# KeyboardMoudle1.net
KiCad netlist of a schematic drawn in Altium Designer
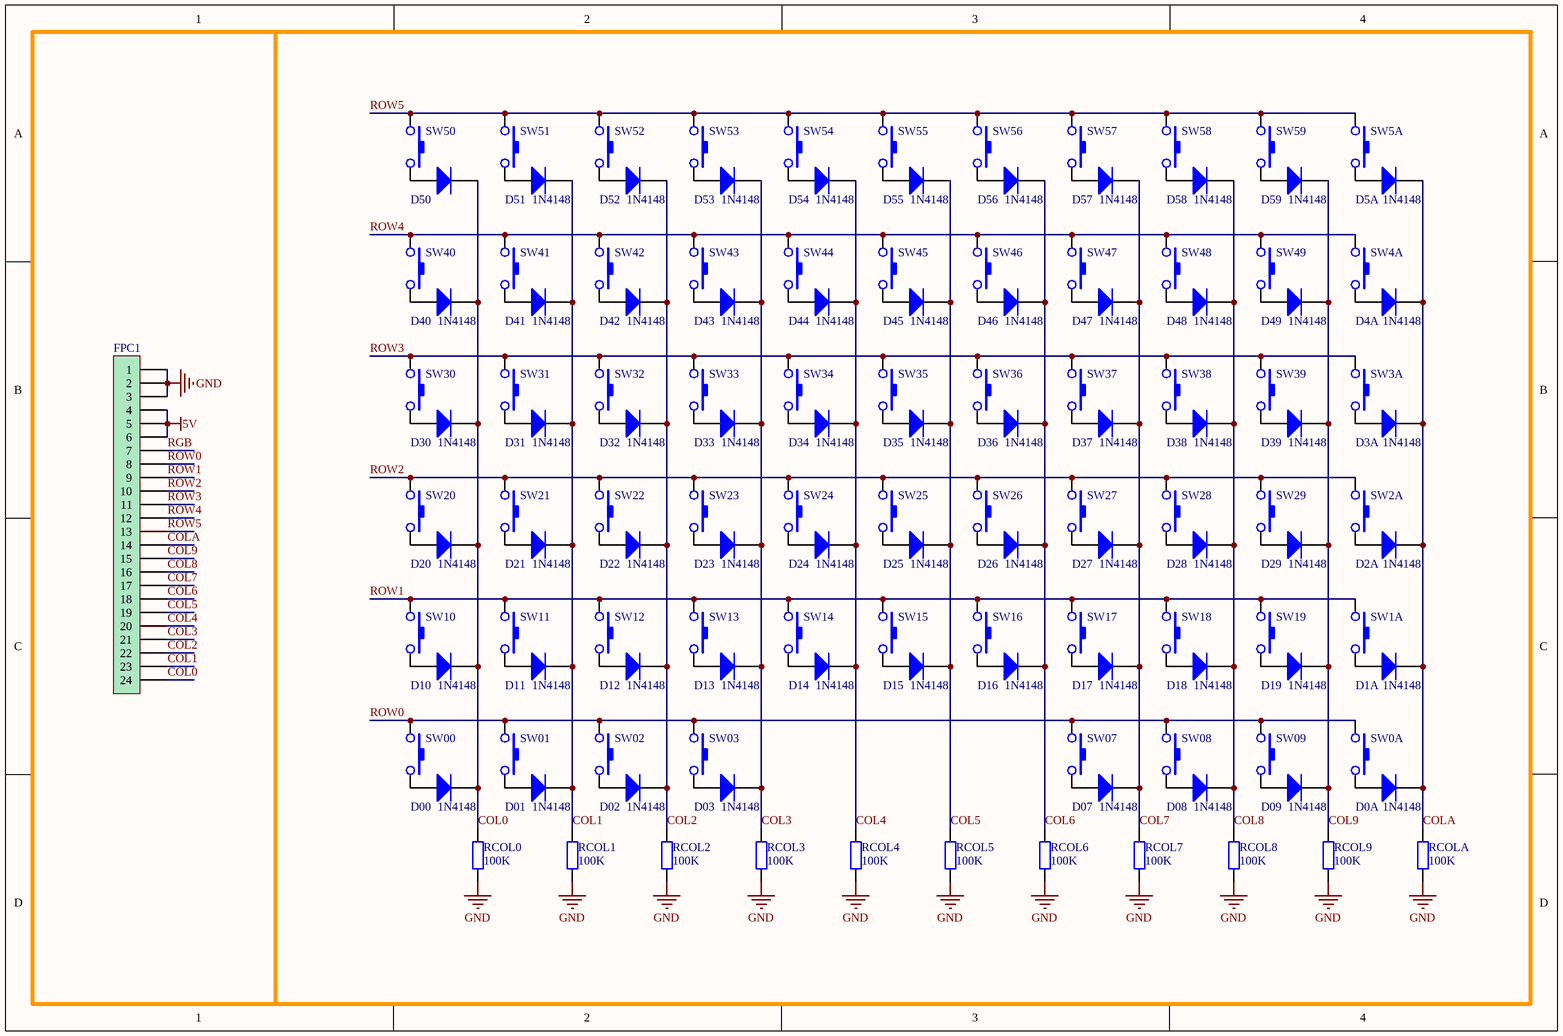
[diagram p0: KeyboardMoudle1.SchDoc]

(export (version "E")
  (design (tool "Eeschema 10.0.6"))
  (components
    (comp (ref "D00")
      (value "1N4148")
      (footprint "SOD523")
      (description "开关二极管")
      (libsource (lib "MT_Device") (part "DIO_1N4148_SOD523"))
    )
    (comp (ref "D0A")
      (value "1N4148")
      (footprint "SOD523")
      (description "开关二极管")
      (libsource (lib "MT_Device") (part "DIO_1N4148_SOD523"))
    )
    (comp (ref "D01")
      (value "1N4148")
      (footprint "SOD523")
      (description "开关二极管")
      (libsource (lib "MT_Device") (part "DIO_1N4148_SOD523"))
    )
    (comp (ref "D1A")
      (value "1N4148")
      (footprint "SOD523")
      (description "开关二极管")
      (libsource (lib "MT_Device") (part "DIO_1N4148_SOD523"))
    )
    (comp (ref "D02")
      (value "1N4148")
      (footprint "SOD523")
      (description "开关二极管")
      (libsource (lib "MT_Device") (part "DIO_1N4148_SOD523"))
    )
    (comp (ref "D2A")
      (value "1N4148")
      (footprint "SOD523")
      (description "开关二极管")
      (libsource (lib "MT_Device") (part "DIO_1N4148_SOD523"))
    )
    (comp (ref "D03")
      (value "1N4148")
      (footprint "SOD523")
      (description "开关二极管")
      (libsource (lib "MT_Device") (part "DIO_1N4148_SOD523"))
    )
    (comp (ref "D3A")
      (value "1N4148")
      (footprint "SOD523")
      (description "开关二极管")
      (libsource (lib "MT_Device") (part "DIO_1N4148_SOD523"))
    )
    (comp (ref "D4A")
      (value "1N4148")
      (footprint "SOD523")
      (description "开关二极管")
      (libsource (lib "MT_Device") (part "DIO_1N4148_SOD523"))
    )
    (comp (ref "D5A")
      (value "1N4148")
      (footprint "SOD523")
      (description "开关二极管")
      (libsource (lib "MT_Device") (part "DIO_1N4148_SOD523"))
    )
    (comp (ref "D07")
      (value "1N4148")
      (footprint "SOD523")
      (description "开关二极管")
      (libsource (lib "MT_Device") (part "DIO_1N4148_SOD523"))
    )
    (comp (ref "D08")
      (value "1N4148")
      (footprint "SOD523")
      (description "开关二极管")
      (libsource (lib "MT_Device") (part "DIO_1N4148_SOD523"))
    )
    (comp (ref "D09")
      (value "1N4148")
      (footprint "SOD523")
      (description "开关二极管")
      (libsource (lib "MT_Device") (part "DIO_1N4148_SOD523"))
    )
    (comp (ref "D10")
      (value "1N4148")
      (footprint "SOD523")
      (description "开关二极管")
      (libsource (lib "MT_Device") (part "DIO_1N4148_SOD523"))
    )
    (comp (ref "D11")
      (value "1N4148")
      (footprint "SOD523")
      (description "开关二极管")
      (libsource (lib "MT_Device") (part "DIO_1N4148_SOD523"))
    )
    (comp (ref "D12")
      (value "1N4148")
      (footprint "SOD523")
      (description "开关二极管")
      (libsource (lib "MT_Device") (part "DIO_1N4148_SOD523"))
    )
    (comp (ref "D13")
      (value "1N4148")
      (footprint "SOD523")
      (description "开关二极管")
      (libsource (lib "MT_Device") (part "DIO_1N4148_SOD523"))
    )
    (comp (ref "D14")
      (value "1N4148")
      (footprint "SOD523")
      (description "开关二极管")
      (libsource (lib "MT_Device") (part "DIO_1N4148_SOD523"))
    )
    (comp (ref "D15")
      (value "1N4148")
      (footprint "SOD523")
      (description "开关二极管")
      (libsource (lib "MT_Device") (part "DIO_1N4148_SOD523"))
    )
    (comp (ref "D16")
      (value "1N4148")
      (footprint "SOD523")
      (description "开关二极管")
      (libsource (lib "MT_Device") (part "DIO_1N4148_SOD523"))
    )
    (comp (ref "D17")
      (value "1N4148")
      (footprint "SOD523")
      (description "开关二极管")
      (libsource (lib "MT_Device") (part "DIO_1N4148_SOD523"))
    )
    (comp (ref "D18")
      (value "1N4148")
      (footprint "SOD523")
      (description "开关二极管")
      (libsource (lib "MT_Device") (part "DIO_1N4148_SOD523"))
    )
    (comp (ref "D19")
      (value "1N4148")
      (footprint "SOD523")
      (description "开关二极管")
      (libsource (lib "MT_Device") (part "DIO_1N4148_SOD523"))
    )
    (comp (ref "D20")
      (value "1N4148")
      (footprint "SOD523")
      (description "开关二极管")
      (libsource (lib "MT_Device") (part "DIO_1N4148_SOD523"))
    )
    (comp (ref "D21")
      (value "1N4148")
      (footprint "SOD523")
      (description "开关二极管")
      (libsource (lib "MT_Device") (part "DIO_1N4148_SOD523"))
    )
    (comp (ref "D22")
      (value "1N4148")
      (footprint "SOD523")
      (description "开关二极管")
      (libsource (lib "MT_Device") (part "DIO_1N4148_SOD523"))
    )
    (comp (ref "D23")
      (value "1N4148")
      (footprint "SOD523")
      (description "开关二极管")
      (libsource (lib "MT_Device") (part "DIO_1N4148_SOD523"))
    )
    (comp (ref "D24")
      (value "1N4148")
      (footprint "SOD523")
      (description "开关二极管")
      (libsource (lib "MT_Device") (part "DIO_1N4148_SOD523"))
    )
    (comp (ref "D25")
      (value "1N4148")
      (footprint "SOD523")
      (description "开关二极管")
      (libsource (lib "MT_Device") (part "DIO_1N4148_SOD523"))
    )
    (comp (ref "D26")
      (value "1N4148")
      (footprint "SOD523")
      (description "开关二极管")
      (libsource (lib "MT_Device") (part "DIO_1N4148_SOD523"))
    )
    (comp (ref "D27")
      (value "1N4148")
      (footprint "SOD523")
      (description "开关二极管")
      (libsource (lib "MT_Device") (part "DIO_1N4148_SOD523"))
    )
    (comp (ref "D28")
      (value "1N4148")
      (footprint "SOD523")
      (description "开关二极管")
      (libsource (lib "MT_Device") (part "DIO_1N4148_SOD523"))
    )
    (comp (ref "D29")
      (value "1N4148")
      (footprint "SOD523")
      (description "开关二极管")
      (libsource (lib "MT_Device") (part "DIO_1N4148_SOD523"))
    )
    (comp (ref "D30")
      (value "1N4148")
      (footprint "SOD523")
      (description "开关二极管")
      (libsource (lib "MT_Device") (part "DIO_1N4148_SOD523"))
    )
    (comp (ref "D31")
      (value "1N4148")
      (footprint "SOD523")
      (description "开关二极管")
      (libsource (lib "MT_Device") (part "DIO_1N4148_SOD523"))
    )
    (comp (ref "D32")
      (value "1N4148")
      (footprint "SOD523")
      (description "开关二极管")
      (libsource (lib "MT_Device") (part "DIO_1N4148_SOD523"))
    )
    (comp (ref "D33")
      (value "1N4148")
      (footprint "SOD523")
      (description "开关二极管")
      (libsource (lib "MT_Device") (part "DIO_1N4148_SOD523"))
    )
    (comp (ref "D34")
      (value "1N4148")
      (footprint "SOD523")
      (description "开关二极管")
      (libsource (lib "MT_Device") (part "DIO_1N4148_SOD523"))
    )
    (comp (ref "D35")
      (value "1N4148")
      (footprint "SOD523")
      (description "开关二极管")
      (libsource (lib "MT_Device") (part "DIO_1N4148_SOD523"))
    )
    (comp (ref "D36")
      (value "1N4148")
      (footprint "SOD523")
      (description "开关二极管")
      (libsource (lib "MT_Device") (part "DIO_1N4148_SOD523"))
    )
    (comp (ref "D37")
      (value "1N4148")
      (footprint "SOD523")
      (description "开关二极管")
      (libsource (lib "MT_Device") (part "DIO_1N4148_SOD523"))
    )
    (comp (ref "D38")
      (value "1N4148")
      (footprint "SOD523")
      (description "开关二极管")
      (libsource (lib "MT_Device") (part "DIO_1N4148_SOD523"))
    )
    (comp (ref "D39")
      (value "1N4148")
      (footprint "SOD523")
      (description "开关二极管")
      (libsource (lib "MT_Device") (part "DIO_1N4148_SOD523"))
    )
    (comp (ref "D40")
      (value "1N4148")
      (footprint "SOD523")
      (description "开关二极管")
      (libsource (lib "MT_Device") (part "DIO_1N4148_SOD523"))
    )
    (comp (ref "D41")
      (value "1N4148")
      (footprint "SOD523")
      (description "开关二极管")
      (libsource (lib "MT_Device") (part "DIO_1N4148_SOD523"))
    )
    (comp (ref "D42")
      (value "1N4148")
      (footprint "SOD523")
      (description "开关二极管")
      (libsource (lib "MT_Device") (part "DIO_1N4148_SOD523"))
    )
    (comp (ref "D43")
      (value "1N4148")
      (footprint "SOD523")
      (description "开关二极管")
      (libsource (lib "MT_Device") (part "DIO_1N4148_SOD523"))
    )
    (comp (ref "D44")
      (value "1N4148")
      (footprint "SOD523")
      (description "开关二极管")
      (libsource (lib "MT_Device") (part "DIO_1N4148_SOD523"))
    )
    (comp (ref "D45")
      (value "1N4148")
      (footprint "SOD523")
      (description "开关二极管")
      (libsource (lib "MT_Device") (part "DIO_1N4148_SOD523"))
    )
    (comp (ref "D46")
      (value "1N4148")
      (footprint "SOD523")
      (description "开关二极管")
      (libsource (lib "MT_Device") (part "DIO_1N4148_SOD523"))
    )
    (comp (ref "D47")
      (value "1N4148")
      (footprint "SOD523")
      (description "开关二极管")
      (libsource (lib "MT_Device") (part "DIO_1N4148_SOD523"))
    )
    (comp (ref "D48")
      (value "1N4148")
      (footprint "SOD523")
      (description "开关二极管")
      (libsource (lib "MT_Device") (part "DIO_1N4148_SOD523"))
    )
    (comp (ref "D49")
      (value "1N4148")
      (footprint "SOD523")
      (description "开关二极管")
      (libsource (lib "MT_Device") (part "DIO_1N4148_SOD523"))
    )
    (comp (ref "D50")
      (value "~")
      (footprint "SOD523")
      (description "开关二极管")
      (libsource (lib "MT_Device") (part "DIO_1N4148_SOD523"))
    )
    (comp (ref "D51")
      (value "1N4148")
      (footprint "SOD523")
      (description "开关二极管")
      (libsource (lib "MT_Device") (part "DIO_1N4148_SOD523"))
    )
    (comp (ref "D52")
      (value "1N4148")
      (footprint "SOD523")
      (description "开关二极管")
      (libsource (lib "MT_Device") (part "DIO_1N4148_SOD523"))
    )
    (comp (ref "D53")
      (value "1N4148")
      (footprint "SOD523")
      (description "开关二极管")
      (libsource (lib "MT_Device") (part "DIO_1N4148_SOD523"))
    )
    (comp (ref "D54")
      (value "1N4148")
      (footprint "SOD523")
      (description "开关二极管")
      (libsource (lib "MT_Device") (part "DIO_1N4148_SOD523"))
    )
    (comp (ref "D55")
      (value "1N4148")
      (footprint "SOD523")
      (description "开关二极管")
      (libsource (lib "MT_Device") (part "DIO_1N4148_SOD523"))
    )
    (comp (ref "D56")
      (value "1N4148")
      (footprint "SOD523")
      (description "开关二极管")
      (libsource (lib "MT_Device") (part "DIO_1N4148_SOD523"))
    )
    (comp (ref "D57")
      (value "1N4148")
      (footprint "SOD523")
      (description "开关二极管")
      (libsource (lib "MT_Device") (part "DIO_1N4148_SOD523"))
    )
    (comp (ref "D58")
      (value "1N4148")
      (footprint "SOD523")
      (description "开关二极管")
      (libsource (lib "MT_Device") (part "DIO_1N4148_SOD523"))
    )
    (comp (ref "D59")
      (value "1N4148")
      (footprint "SOD523")
      (description "开关二极管")
      (libsource (lib "MT_Device") (part "DIO_1N4148_SOD523"))
    )
    (comp (ref "FPC1")
      (value "FPC_0.5_24P")
      (footprint "FPC_0.5_24PIN")
      (description "FPC 0.5 24Pin")
      (libsource (lib "MT_Connector") (part "FPC_0.5_24P"))
    )
    (comp (ref "RCOL0")
      (value "100K")
      (footprint "R_0603")
      (description "电阻 0603")
      (libsource (lib "MT_Device") (part "RES_0603"))
    )
    (comp (ref "RCOL1")
      (value "100K")
      (footprint "R_0603")
      (description "电阻 0603")
      (libsource (lib "MT_Device") (part "RES_0603"))
    )
    (comp (ref "RCOL2")
      (value "100K")
      (footprint "R_0603")
      (description "电阻 0603")
      (libsource (lib "MT_Device") (part "RES_0603"))
    )
    (comp (ref "RCOL3")
      (value "100K")
      (footprint "R_0603")
      (description "电阻 0603")
      (libsource (lib "MT_Device") (part "RES_0603"))
    )
    (comp (ref "RCOL4")
      (value "100K")
      (footprint "R_0603")
      (description "电阻 0603")
      (libsource (lib "MT_Device") (part "RES_0603"))
    )
    (comp (ref "RCOL5")
      (value "100K")
      (footprint "R_0603")
      (description "电阻 0603")
      (libsource (lib "MT_Device") (part "RES_0603"))
    )
    (comp (ref "RCOL6")
      (value "100K")
      (footprint "R_0603")
      (description "电阻 0603")
      (libsource (lib "MT_Device") (part "RES_0603"))
    )
    (comp (ref "RCOL7")
      (value "100K")
      (footprint "R_0603")
      (description "电阻 0603")
      (libsource (lib "MT_Device") (part "RES_0603"))
    )
    (comp (ref "RCOL8")
      (value "100K")
      (footprint "R_0603")
      (description "电阻 0603")
      (libsource (lib "MT_Device") (part "RES_0603"))
    )
    (comp (ref "RCOL9")
      (value "100K")
      (footprint "R_0603")
      (description "电阻 0603")
      (libsource (lib "MT_Device") (part "RES_0603"))
    )
    (comp (ref "RCOLA")
      (value "100K")
      (footprint "R_0603")
      (description "电阻 0603")
      (libsource (lib "MT_Device") (part "RES_0603"))
    )
    (comp (ref "SW00")
      (value "KAILH")
      (footprint "KAILH_1350_HOTSWAP")
      (description "凯华机械矮轴1350用热插拔轴座")
      (libsource (lib "MT_Device") (part "SWITCH_KAILH_1350"))
    )
    (comp (ref "SW0A")
      (value "KAILH")
      (footprint "KAILH_1350_HOTSWAP")
      (description "凯华机械矮轴1350用热插拔轴座")
      (libsource (lib "MT_Device") (part "SWITCH_KAILH_1350"))
    )
    (comp (ref "SW01")
      (value "KAILH")
      (footprint "KAILH_1350_HOTSWAP")
      (description "凯华机械矮轴1350用热插拔轴座")
      (libsource (lib "MT_Device") (part "SWITCH_KAILH_1350"))
    )
    (comp (ref "SW1A")
      (value "KAILH")
      (footprint "KAILH_1350_HOTSWAP")
      (description "凯华机械矮轴1350用热插拔轴座")
      (libsource (lib "MT_Device") (part "SWITCH_KAILH_1350"))
    )
    (comp (ref "SW02")
      (value "KAILH")
      (footprint "KAILH_1350_HOTSWAP")
      (description "凯华机械矮轴1350用热插拔轴座")
      (libsource (lib "MT_Device") (part "SWITCH_KAILH_1350"))
    )
    (comp (ref "SW2A")
      (value "KAILH")
      (footprint "KAILH_1350_HOTSWAP")
      (description "凯华机械矮轴1350用热插拔轴座")
      (libsource (lib "MT_Device") (part "SWITCH_KAILH_1350"))
    )
    (comp (ref "SW03")
      (value "KAILH")
      (footprint "KAILH_1350_HOTSWAP")
      (description "凯华机械矮轴1350用热插拔轴座")
      (libsource (lib "MT_Device") (part "SWITCH_KAILH_1350"))
    )
    (comp (ref "SW3A")
      (value "KAILH")
      (footprint "KAILH_1350_HOTSWAP")
      (description "凯华机械矮轴1350用热插拔轴座")
      (libsource (lib "MT_Device") (part "SWITCH_KAILH_1350"))
    )
    (comp (ref "SW4A")
      (value "KAILH")
      (footprint "KAILH_1350_HOTSWAP")
      (description "凯华机械矮轴1350用热插拔轴座")
      (libsource (lib "MT_Device") (part "SWITCH_KAILH_1350"))
    )
    (comp (ref "SW5A")
      (value "KAILH")
      (footprint "KAILH_1350_HOTSWAP")
      (description "凯华机械矮轴1350用热插拔轴座")
      (libsource (lib "MT_Device") (part "SWITCH_KAILH_1350"))
    )
    (comp (ref "SW07")
      (value "KAILH")
      (footprint "KAILH_1350_HOTSWAP")
      (description "凯华机械矮轴1350用热插拔轴座")
      (libsource (lib "MT_Device") (part "SWITCH_KAILH_1350"))
    )
    (comp (ref "SW08")
      (value "KAILH")
      (footprint "KAILH_1350_HOTSWAP")
      (description "凯华机械矮轴1350用热插拔轴座")
      (libsource (lib "MT_Device") (part "SWITCH_KAILH_1350"))
    )
    (comp (ref "SW09")
      (value "KAILH")
      (footprint "KAILH_1350_HOTSWAP")
      (description "凯华机械矮轴1350用热插拔轴座")
      (libsource (lib "MT_Device") (part "SWITCH_KAILH_1350"))
    )
    (comp (ref "SW10")
      (value "KAILH")
      (footprint "KAILH_1350_HOTSWAP")
      (description "凯华机械矮轴1350用热插拔轴座")
      (libsource (lib "MT_Device") (part "SWITCH_KAILH_1350"))
    )
    (comp (ref "SW11")
      (value "KAILH")
      (footprint "KAILH_1350_HOTSWAP")
      (description "凯华机械矮轴1350用热插拔轴座")
      (libsource (lib "MT_Device") (part "SWITCH_KAILH_1350"))
    )
    (comp (ref "SW12")
      (value "KAILH")
      (footprint "KAILH_1350_HOTSWAP")
      (description "凯华机械矮轴1350用热插拔轴座")
      (libsource (lib "MT_Device") (part "SWITCH_KAILH_1350"))
    )
    (comp (ref "SW13")
      (value "KAILH")
      (footprint "KAILH_1350_HOTSWAP")
      (description "凯华机械矮轴1350用热插拔轴座")
      (libsource (lib "MT_Device") (part "SWITCH_KAILH_1350"))
    )
    (comp (ref "SW14")
      (value "KAILH")
      (footprint "KAILH_1350_HOTSWAP")
      (description "凯华机械矮轴1350用热插拔轴座")
      (libsource (lib "MT_Device") (part "SWITCH_KAILH_1350"))
    )
    (comp (ref "SW15")
      (value "KAILH")
      (footprint "KAILH_1350_HOTSWAP")
      (description "凯华机械矮轴1350用热插拔轴座")
      (libsource (lib "MT_Device") (part "SWITCH_KAILH_1350"))
    )
    (comp (ref "SW16")
      (value "KAILH")
      (footprint "KAILH_1350_HOTSWAP")
      (description "凯华机械矮轴1350用热插拔轴座")
      (libsource (lib "MT_Device") (part "SWITCH_KAILH_1350"))
    )
    (comp (ref "SW17")
      (value "KAILH")
      (footprint "KAILH_1350_HOTSWAP")
      (description "凯华机械矮轴1350用热插拔轴座")
      (libsource (lib "MT_Device") (part "SWITCH_KAILH_1350"))
    )
    (comp (ref "SW18")
      (value "KAILH")
      (footprint "KAILH_1350_HOTSWAP")
      (description "凯华机械矮轴1350用热插拔轴座")
      (libsource (lib "MT_Device") (part "SWITCH_KAILH_1350"))
    )
    (comp (ref "SW19")
      (value "KAILH")
      (footprint "KAILH_1350_HOTSWAP")
      (description "凯华机械矮轴1350用热插拔轴座")
      (libsource (lib "MT_Device") (part "SWITCH_KAILH_1350"))
    )
    (comp (ref "SW20")
      (value "KAILH")
      (footprint "KAILH_1350_HOTSWAP")
      (description "凯华机械矮轴1350用热插拔轴座")
      (libsource (lib "MT_Device") (part "SWITCH_KAILH_1350"))
    )
    (comp (ref "SW21")
      (value "KAILH")
      (footprint "KAILH_1350_HOTSWAP")
      (description "凯华机械矮轴1350用热插拔轴座")
      (libsource (lib "MT_Device") (part "SWITCH_KAILH_1350"))
    )
    (comp (ref "SW22")
      (value "KAILH")
      (footprint "KAILH_1350_HOTSWAP")
      (description "凯华机械矮轴1350用热插拔轴座")
      (libsource (lib "MT_Device") (part "SWITCH_KAILH_1350"))
    )
    (comp (ref "SW23")
      (value "KAILH")
      (footprint "KAILH_1350_HOTSWAP")
      (description "凯华机械矮轴1350用热插拔轴座")
      (libsource (lib "MT_Device") (part "SWITCH_KAILH_1350"))
    )
    (comp (ref "SW24")
      (value "KAILH")
      (footprint "KAILH_1350_HOTSWAP")
      (description "凯华机械矮轴1350用热插拔轴座")
      (libsource (lib "MT_Device") (part "SWITCH_KAILH_1350"))
    )
    (comp (ref "SW25")
      (value "KAILH")
      (footprint "KAILH_1350_HOTSWAP")
      (description "凯华机械矮轴1350用热插拔轴座")
      (libsource (lib "MT_Device") (part "SWITCH_KAILH_1350"))
    )
    (comp (ref "SW26")
      (value "KAILH")
      (footprint "KAILH_1350_HOTSWAP")
      (description "凯华机械矮轴1350用热插拔轴座")
      (libsource (lib "MT_Device") (part "SWITCH_KAILH_1350"))
    )
    (comp (ref "SW27")
      (value "KAILH")
      (footprint "KAILH_1350_HOTSWAP")
      (description "凯华机械矮轴1350用热插拔轴座")
      (libsource (lib "MT_Device") (part "SWITCH_KAILH_1350"))
    )
    (comp (ref "SW28")
      (value "KAILH")
      (footprint "KAILH_1350_HOTSWAP")
      (description "凯华机械矮轴1350用热插拔轴座")
      (libsource (lib "MT_Device") (part "SWITCH_KAILH_1350"))
    )
    (comp (ref "SW29")
      (value "KAILH")
      (footprint "KAILH_1350_HOTSWAP")
      (description "凯华机械矮轴1350用热插拔轴座")
      (libsource (lib "MT_Device") (part "SWITCH_KAILH_1350"))
    )
    (comp (ref "SW30")
      (value "KAILH")
      (footprint "KAILH_1350_HOTSWAP")
      (description "凯华机械矮轴1350用热插拔轴座")
      (libsource (lib "MT_Device") (part "SWITCH_KAILH_1350"))
    )
    (comp (ref "SW31")
      (value "KAILH")
      (footprint "KAILH_1350_HOTSWAP")
      (description "凯华机械矮轴1350用热插拔轴座")
      (libsource (lib "MT_Device") (part "SWITCH_KAILH_1350"))
    )
    (comp (ref "SW32")
      (value "KAILH")
      (footprint "KAILH_1350_HOTSWAP")
      (description "凯华机械矮轴1350用热插拔轴座")
      (libsource (lib "MT_Device") (part "SWITCH_KAILH_1350"))
    )
    (comp (ref "SW33")
      (value "KAILH")
      (footprint "KAILH_1350_HOTSWAP")
      (description "凯华机械矮轴1350用热插拔轴座")
      (libsource (lib "MT_Device") (part "SWITCH_KAILH_1350"))
    )
    (comp (ref "SW34")
      (value "KAILH")
      (footprint "KAILH_1350_HOTSWAP")
      (description "凯华机械矮轴1350用热插拔轴座")
      (libsource (lib "MT_Device") (part "SWITCH_KAILH_1350"))
    )
    (comp (ref "SW35")
      (value "KAILH")
      (footprint "KAILH_1350_HOTSWAP")
      (description "凯华机械矮轴1350用热插拔轴座")
      (libsource (lib "MT_Device") (part "SWITCH_KAILH_1350"))
    )
    (comp (ref "SW36")
      (value "KAILH")
      (footprint "KAILH_1350_HOTSWAP")
      (description "凯华机械矮轴1350用热插拔轴座")
      (libsource (lib "MT_Device") (part "SWITCH_KAILH_1350"))
    )
    (comp (ref "SW37")
      (value "KAILH")
      (footprint "KAILH_1350_HOTSWAP")
      (description "凯华机械矮轴1350用热插拔轴座")
      (libsource (lib "MT_Device") (part "SWITCH_KAILH_1350"))
    )
    (comp (ref "SW38")
      (value "KAILH")
      (footprint "KAILH_1350_HOTSWAP")
      (description "凯华机械矮轴1350用热插拔轴座")
      (libsource (lib "MT_Device") (part "SWITCH_KAILH_1350"))
    )
    (comp (ref "SW39")
      (value "KAILH")
      (footprint "KAILH_1350_HOTSWAP")
      (description "凯华机械矮轴1350用热插拔轴座")
      (libsource (lib "MT_Device") (part "SWITCH_KAILH_1350"))
    )
    (comp (ref "SW40")
      (value "KAILH")
      (footprint "KAILH_1350_HOTSWAP")
      (description "凯华机械矮轴1350用热插拔轴座")
      (libsource (lib "MT_Device") (part "SWITCH_KAILH_1350"))
    )
    (comp (ref "SW41")
      (value "KAILH")
      (footprint "KAILH_1350_HOTSWAP")
      (description "凯华机械矮轴1350用热插拔轴座")
      (libsource (lib "MT_Device") (part "SWITCH_KAILH_1350"))
    )
    (comp (ref "SW42")
      (value "KAILH")
      (footprint "KAILH_1350_HOTSWAP")
      (description "凯华机械矮轴1350用热插拔轴座")
      (libsource (lib "MT_Device") (part "SWITCH_KAILH_1350"))
    )
    (comp (ref "SW43")
      (value "KAILH")
      (footprint "KAILH_1350_HOTSWAP")
      (description "凯华机械矮轴1350用热插拔轴座")
      (libsource (lib "MT_Device") (part "SWITCH_KAILH_1350"))
    )
    (comp (ref "SW44")
      (value "KAILH")
      (footprint "KAILH_1350_HOTSWAP")
      (description "凯华机械矮轴1350用热插拔轴座")
      (libsource (lib "MT_Device") (part "SWITCH_KAILH_1350"))
    )
    (comp (ref "SW45")
      (value "KAILH")
      (footprint "KAILH_1350_HOTSWAP")
      (description "凯华机械矮轴1350用热插拔轴座")
      (libsource (lib "MT_Device") (part "SWITCH_KAILH_1350"))
    )
    (comp (ref "SW46")
      (value "KAILH")
      (footprint "KAILH_1350_HOTSWAP")
      (description "凯华机械矮轴1350用热插拔轴座")
      (libsource (lib "MT_Device") (part "SWITCH_KAILH_1350"))
    )
    (comp (ref "SW47")
      (value "KAILH")
      (footprint "KAILH_1350_HOTSWAP")
      (description "凯华机械矮轴1350用热插拔轴座")
      (libsource (lib "MT_Device") (part "SWITCH_KAILH_1350"))
    )
    (comp (ref "SW48")
      (value "KAILH")
      (footprint "KAILH_1350_HOTSWAP")
      (description "凯华机械矮轴1350用热插拔轴座")
      (libsource (lib "MT_Device") (part "SWITCH_KAILH_1350"))
    )
    (comp (ref "SW49")
      (value "KAILH")
      (footprint "KAILH_1350_HOTSWAP")
      (description "凯华机械矮轴1350用热插拔轴座")
      (libsource (lib "MT_Device") (part "SWITCH_KAILH_1350"))
    )
    (comp (ref "SW50")
      (value "KAILH")
      (footprint "KAILH_1350_HOTSWAP")
      (description "凯华机械矮轴1350用热插拔轴座")
      (libsource (lib "MT_Device") (part "SWITCH_KAILH_1350"))
    )
    (comp (ref "SW51")
      (value "KAILH")
      (footprint "KAILH_1350_HOTSWAP")
      (description "凯华机械矮轴1350用热插拔轴座")
      (libsource (lib "MT_Device") (part "SWITCH_KAILH_1350"))
    )
    (comp (ref "SW52")
      (value "KAILH")
      (footprint "KAILH_1350_HOTSWAP")
      (description "凯华机械矮轴1350用热插拔轴座")
      (libsource (lib "MT_Device") (part "SWITCH_KAILH_1350"))
    )
    (comp (ref "SW53")
      (value "KAILH")
      (footprint "KAILH_1350_HOTSWAP")
      (description "凯华机械矮轴1350用热插拔轴座")
      (libsource (lib "MT_Device") (part "SWITCH_KAILH_1350"))
    )
    (comp (ref "SW54")
      (value "KAILH")
      (footprint "KAILH_1350_HOTSWAP")
      (description "凯华机械矮轴1350用热插拔轴座")
      (libsource (lib "MT_Device") (part "SWITCH_KAILH_1350"))
    )
    (comp (ref "SW55")
      (value "KAILH")
      (footprint "KAILH_1350_HOTSWAP")
      (description "凯华机械矮轴1350用热插拔轴座")
      (libsource (lib "MT_Device") (part "SWITCH_KAILH_1350"))
    )
    (comp (ref "SW56")
      (value "KAILH")
      (footprint "KAILH_1350_HOTSWAP")
      (description "凯华机械矮轴1350用热插拔轴座")
      (libsource (lib "MT_Device") (part "SWITCH_KAILH_1350"))
    )
    (comp (ref "SW57")
      (value "KAILH")
      (footprint "KAILH_1350_HOTSWAP")
      (description "凯华机械矮轴1350用热插拔轴座")
      (libsource (lib "MT_Device") (part "SWITCH_KAILH_1350"))
    )
    (comp (ref "SW58")
      (value "KAILH")
      (footprint "KAILH_1350_HOTSWAP")
      (description "凯华机械矮轴1350用热插拔轴座")
      (libsource (lib "MT_Device") (part "SWITCH_KAILH_1350"))
    )
    (comp (ref "SW59")
      (value "KAILH")
      (footprint "KAILH_1350_HOTSWAP")
      (description "凯华机械矮轴1350用热插拔轴座")
      (libsource (lib "MT_Device") (part "SWITCH_KAILH_1350"))
    )
  )
  (nets
    (net (code "1") (name "/COL0") (class "Default")
      (node (ref "D00") (pin "2") (pinfunction "K_2") (pintype "passive"))
      (node (ref "D10") (pin "2") (pinfunction "K_2") (pintype "passive"))
      (node (ref "D20") (pin "2") (pinfunction "K_2") (pintype "passive"))
      (node (ref "D30") (pin "2") (pinfunction "K_2") (pintype "passive"))
      (node (ref "D40") (pin "2") (pinfunction "K_2") (pintype "passive"))
      (node (ref "D50") (pin "2") (pinfunction "K_2") (pintype "passive"))
      (node (ref "FPC1") (pin "24") (pinfunction "24_24") (pintype "passive"))
      (node (ref "RCOL0") (pin "2") (pinfunction "2_2") (pintype "passive"))
    )
    (net (code "2") (name "/COL1") (class "Default")
      (node (ref "D01") (pin "2") (pinfunction "K_2") (pintype "passive"))
      (node (ref "D11") (pin "2") (pinfunction "K_2") (pintype "passive"))
      (node (ref "D21") (pin "2") (pinfunction "K_2") (pintype "passive"))
      (node (ref "D31") (pin "2") (pinfunction "K_2") (pintype "passive"))
      (node (ref "D41") (pin "2") (pinfunction "K_2") (pintype "passive"))
      (node (ref "D51") (pin "2") (pinfunction "K_2") (pintype "passive"))
      (node (ref "FPC1") (pin "23") (pinfunction "23_23") (pintype "passive"))
      (node (ref "RCOL1") (pin "2") (pinfunction "2_2") (pintype "passive"))
    )
    (net (code "3") (name "/COL2") (class "Default")
      (node (ref "D02") (pin "2") (pinfunction "K_2") (pintype "passive"))
      (node (ref "D12") (pin "2") (pinfunction "K_2") (pintype "passive"))
      (node (ref "D22") (pin "2") (pinfunction "K_2") (pintype "passive"))
      (node (ref "D32") (pin "2") (pinfunction "K_2") (pintype "passive"))
      (node (ref "D42") (pin "2") (pinfunction "K_2") (pintype "passive"))
      (node (ref "D52") (pin "2") (pinfunction "K_2") (pintype "passive"))
      (node (ref "FPC1") (pin "22") (pinfunction "22_22") (pintype "passive"))
      (node (ref "RCOL2") (pin "2") (pinfunction "2_2") (pintype "passive"))
    )
    (net (code "4") (name "/COL3") (class "Default")
      (node (ref "D03") (pin "2") (pinfunction "K_2") (pintype "passive"))
      (node (ref "D13") (pin "2") (pinfunction "K_2") (pintype "passive"))
      (node (ref "D23") (pin "2") (pinfunction "K_2") (pintype "passive"))
      (node (ref "D33") (pin "2") (pinfunction "K_2") (pintype "passive"))
      (node (ref "D43") (pin "2") (pinfunction "K_2") (pintype "passive"))
      (node (ref "D53") (pin "2") (pinfunction "K_2") (pintype "passive"))
      (node (ref "FPC1") (pin "21") (pinfunction "21_21") (pintype "passive"))
      (node (ref "RCOL3") (pin "2") (pinfunction "2_2") (pintype "passive"))
    )
    (net (code "5") (name "/COL4") (class "Default")
      (node (ref "D14") (pin "2") (pinfunction "K_2") (pintype "passive"))
      (node (ref "D24") (pin "2") (pinfunction "K_2") (pintype "passive"))
      (node (ref "D34") (pin "2") (pinfunction "K_2") (pintype "passive"))
      (node (ref "D44") (pin "2") (pinfunction "K_2") (pintype "passive"))
      (node (ref "D54") (pin "2") (pinfunction "K_2") (pintype "passive"))
      (node (ref "FPC1") (pin "20") (pinfunction "20_20") (pintype "passive"))
      (node (ref "RCOL4") (pin "2") (pinfunction "2_2") (pintype "passive"))
    )
    (net (code "6") (name "/COL5") (class "Default")
      (node (ref "D15") (pin "2") (pinfunction "K_2") (pintype "passive"))
      (node (ref "D25") (pin "2") (pinfunction "K_2") (pintype "passive"))
      (node (ref "D35") (pin "2") (pinfunction "K_2") (pintype "passive"))
      (node (ref "D45") (pin "2") (pinfunction "K_2") (pintype "passive"))
      (node (ref "D55") (pin "2") (pinfunction "K_2") (pintype "passive"))
      (node (ref "FPC1") (pin "19") (pinfunction "19_19") (pintype "passive"))
      (node (ref "RCOL5") (pin "2") (pinfunction "2_2") (pintype "passive"))
    )
    (net (code "7") (name "/COL6") (class "Default")
      (node (ref "D16") (pin "2") (pinfunction "K_2") (pintype "passive"))
      (node (ref "D26") (pin "2") (pinfunction "K_2") (pintype "passive"))
      (node (ref "D36") (pin "2") (pinfunction "K_2") (pintype "passive"))
      (node (ref "D46") (pin "2") (pinfunction "K_2") (pintype "passive"))
      (node (ref "D56") (pin "2") (pinfunction "K_2") (pintype "passive"))
      (node (ref "FPC1") (pin "18") (pinfunction "18_18") (pintype "passive"))
      (node (ref "RCOL6") (pin "2") (pinfunction "2_2") (pintype "passive"))
    )
    (net (code "8") (name "/COL7") (class "Default")
      (node (ref "D07") (pin "2") (pinfunction "K_2") (pintype "passive"))
      (node (ref "D17") (pin "2") (pinfunction "K_2") (pintype "passive"))
      (node (ref "D27") (pin "2") (pinfunction "K_2") (pintype "passive"))
      (node (ref "D37") (pin "2") (pinfunction "K_2") (pintype "passive"))
      (node (ref "D47") (pin "2") (pinfunction "K_2") (pintype "passive"))
      (node (ref "D57") (pin "2") (pinfunction "K_2") (pintype "passive"))
      (node (ref "FPC1") (pin "17") (pinfunction "17_17") (pintype "passive"))
      (node (ref "RCOL7") (pin "2") (pinfunction "2_2") (pintype "passive"))
    )
    (net (code "9") (name "/COL8") (class "Default")
      (node (ref "D08") (pin "2") (pinfunction "K_2") (pintype "passive"))
      (node (ref "D18") (pin "2") (pinfunction "K_2") (pintype "passive"))
      (node (ref "D28") (pin "2") (pinfunction "K_2") (pintype "passive"))
      (node (ref "D38") (pin "2") (pinfunction "K_2") (pintype "passive"))
      (node (ref "D48") (pin "2") (pinfunction "K_2") (pintype "passive"))
      (node (ref "D58") (pin "2") (pinfunction "K_2") (pintype "passive"))
      (node (ref "FPC1") (pin "16") (pinfunction "16_16") (pintype "passive"))
      (node (ref "RCOL8") (pin "2") (pinfunction "2_2") (pintype "passive"))
    )
    (net (code "10") (name "/COL9") (class "Default")
      (node (ref "D09") (pin "2") (pinfunction "K_2") (pintype "passive"))
      (node (ref "D19") (pin "2") (pinfunction "K_2") (pintype "passive"))
      (node (ref "D29") (pin "2") (pinfunction "K_2") (pintype "passive"))
      (node (ref "D39") (pin "2") (pinfunction "K_2") (pintype "passive"))
      (node (ref "D49") (pin "2") (pinfunction "K_2") (pintype "passive"))
      (node (ref "D59") (pin "2") (pinfunction "K_2") (pintype "passive"))
      (node (ref "FPC1") (pin "15") (pinfunction "15_15") (pintype "passive"))
      (node (ref "RCOL9") (pin "2") (pinfunction "2_2") (pintype "passive"))
    )
    (net (code "11") (name "/COLA") (class "Default")
      (node (ref "D0A") (pin "2") (pinfunction "K_2") (pintype "passive"))
      (node (ref "D1A") (pin "2") (pinfunction "K_2") (pintype "passive"))
      (node (ref "D2A") (pin "2") (pinfunction "K_2") (pintype "passive"))
      (node (ref "D3A") (pin "2") (pinfunction "K_2") (pintype "passive"))
      (node (ref "D4A") (pin "2") (pinfunction "K_2") (pintype "passive"))
      (node (ref "D5A") (pin "2") (pinfunction "K_2") (pintype "passive"))
      (node (ref "FPC1") (pin "14") (pinfunction "14_14") (pintype "passive"))
      (node (ref "RCOLA") (pin "2") (pinfunction "2_2") (pintype "passive"))
    )
    (net (code "12") (name "/RGB") (class "Default")
      (node (ref "FPC1") (pin "7") (pinfunction "7_7") (pintype "passive"))
    )
    (net (code "13") (name "/ROW0") (class "Default")
      (node (ref "FPC1") (pin "8") (pinfunction "8_8") (pintype "passive"))
      (node (ref "SW00") (pin "1") (pinfunction "1_1") (pintype "passive"))
      (node (ref "SW01") (pin "1") (pinfunction "1_1") (pintype "passive"))
      (node (ref "SW02") (pin "1") (pinfunction "1_1") (pintype "passive"))
      (node (ref "SW03") (pin "1") (pinfunction "1_1") (pintype "passive"))
      (node (ref "SW07") (pin "1") (pinfunction "1_1") (pintype "passive"))
      (node (ref "SW08") (pin "1") (pinfunction "1_1") (pintype "passive"))
      (node (ref "SW09") (pin "1") (pinfunction "1_1") (pintype "passive"))
      (node (ref "SW0A") (pin "1") (pinfunction "1_1") (pintype "passive"))
    )
    (net (code "14") (name "/ROW1") (class "Default")
      (node (ref "FPC1") (pin "9") (pinfunction "9_9") (pintype "passive"))
      (node (ref "SW10") (pin "1") (pinfunction "1_1") (pintype "passive"))
      (node (ref "SW11") (pin "1") (pinfunction "1_1") (pintype "passive"))
      (node (ref "SW12") (pin "1") (pinfunction "1_1") (pintype "passive"))
      (node (ref "SW13") (pin "1") (pinfunction "1_1") (pintype "passive"))
      (node (ref "SW14") (pin "1") (pinfunction "1_1") (pintype "passive"))
      (node (ref "SW15") (pin "1") (pinfunction "1_1") (pintype "passive"))
      (node (ref "SW16") (pin "1") (pinfunction "1_1") (pintype "passive"))
      (node (ref "SW17") (pin "1") (pinfunction "1_1") (pintype "passive"))
      (node (ref "SW18") (pin "1") (pinfunction "1_1") (pintype "passive"))
      (node (ref "SW19") (pin "1") (pinfunction "1_1") (pintype "passive"))
      (node (ref "SW1A") (pin "1") (pinfunction "1_1") (pintype "passive"))
    )
    (net (code "15") (name "/ROW2") (class "Default")
      (node (ref "FPC1") (pin "10") (pinfunction "10_10") (pintype "passive"))
      (node (ref "SW20") (pin "1") (pinfunction "1_1") (pintype "passive"))
      (node (ref "SW21") (pin "1") (pinfunction "1_1") (pintype "passive"))
      (node (ref "SW22") (pin "1") (pinfunction "1_1") (pintype "passive"))
      (node (ref "SW23") (pin "1") (pinfunction "1_1") (pintype "passive"))
      (node (ref "SW24") (pin "1") (pinfunction "1_1") (pintype "passive"))
      (node (ref "SW25") (pin "1") (pinfunction "1_1") (pintype "passive"))
      (node (ref "SW26") (pin "1") (pinfunction "1_1") (pintype "passive"))
      (node (ref "SW27") (pin "1") (pinfunction "1_1") (pintype "passive"))
      (node (ref "SW28") (pin "1") (pinfunction "1_1") (pintype "passive"))
      (node (ref "SW29") (pin "1") (pinfunction "1_1") (pintype "passive"))
      (node (ref "SW2A") (pin "1") (pinfunction "1_1") (pintype "passive"))
    )
    (net (code "16") (name "/ROW3") (class "Default")
      (node (ref "FPC1") (pin "11") (pinfunction "11_11") (pintype "passive"))
      (node (ref "SW30") (pin "1") (pinfunction "1_1") (pintype "passive"))
      (node (ref "SW31") (pin "1") (pinfunction "1_1") (pintype "passive"))
      (node (ref "SW32") (pin "1") (pinfunction "1_1") (pintype "passive"))
      (node (ref "SW33") (pin "1") (pinfunction "1_1") (pintype "passive"))
      (node (ref "SW34") (pin "1") (pinfunction "1_1") (pintype "passive"))
      (node (ref "SW35") (pin "1") (pinfunction "1_1") (pintype "passive"))
      (node (ref "SW36") (pin "1") (pinfunction "1_1") (pintype "passive"))
      (node (ref "SW37") (pin "1") (pinfunction "1_1") (pintype "passive"))
      (node (ref "SW38") (pin "1") (pinfunction "1_1") (pintype "passive"))
      (node (ref "SW39") (pin "1") (pinfunction "1_1") (pintype "passive"))
      (node (ref "SW3A") (pin "1") (pinfunction "1_1") (pintype "passive"))
    )
    (net (code "17") (name "/ROW4") (class "Default")
      (node (ref "FPC1") (pin "12") (pinfunction "12_12") (pintype "passive"))
      (node (ref "SW40") (pin "1") (pinfunction "1_1") (pintype "passive"))
      (node (ref "SW41") (pin "1") (pinfunction "1_1") (pintype "passive"))
      (node (ref "SW42") (pin "1") (pinfunction "1_1") (pintype "passive"))
      (node (ref "SW43") (pin "1") (pinfunction "1_1") (pintype "passive"))
      (node (ref "SW44") (pin "1") (pinfunction "1_1") (pintype "passive"))
      (node (ref "SW45") (pin "1") (pinfunction "1_1") (pintype "passive"))
      (node (ref "SW46") (pin "1") (pinfunction "1_1") (pintype "passive"))
      (node (ref "SW47") (pin "1") (pinfunction "1_1") (pintype "passive"))
      (node (ref "SW48") (pin "1") (pinfunction "1_1") (pintype "passive"))
      (node (ref "SW49") (pin "1") (pinfunction "1_1") (pintype "passive"))
      (node (ref "SW4A") (pin "1") (pinfunction "1_1") (pintype "passive"))
    )
    (net (code "18") (name "/ROW5") (class "Default")
      (node (ref "FPC1") (pin "13") (pinfunction "13_13") (pintype "passive"))
      (node (ref "SW50") (pin "1") (pinfunction "1_1") (pintype "passive"))
      (node (ref "SW51") (pin "1") (pinfunction "1_1") (pintype "passive"))
      (node (ref "SW52") (pin "1") (pinfunction "1_1") (pintype "passive"))
      (node (ref "SW53") (pin "1") (pinfunction "1_1") (pintype "passive"))
      (node (ref "SW54") (pin "1") (pinfunction "1_1") (pintype "passive"))
      (node (ref "SW55") (pin "1") (pinfunction "1_1") (pintype "passive"))
      (node (ref "SW56") (pin "1") (pinfunction "1_1") (pintype "passive"))
      (node (ref "SW57") (pin "1") (pinfunction "1_1") (pintype "passive"))
      (node (ref "SW58") (pin "1") (pinfunction "1_1") (pintype "passive"))
      (node (ref "SW59") (pin "1") (pinfunction "1_1") (pintype "passive"))
      (node (ref "SW5A") (pin "1") (pinfunction "1_1") (pintype "passive"))
    )
    (net (code "19") (name "5V") (class "Default")
      (node (ref "FPC1") (pin "4") (pinfunction "4_4") (pintype "passive"))
      (node (ref "FPC1") (pin "5") (pinfunction "5_5") (pintype "passive"))
      (node (ref "FPC1") (pin "6") (pinfunction "6_6") (pintype "passive"))
    )
    (net (code "20") (name "GND") (class "Default")
      (node (ref "FPC1") (pin "1") (pinfunction "1_1") (pintype "passive"))
      (node (ref "FPC1") (pin "2") (pinfunction "2_2") (pintype "passive"))
      (node (ref "FPC1") (pin "3") (pinfunction "3_3") (pintype "passive"))
      (node (ref "RCOL0") (pin "1") (pinfunction "1_1") (pintype "passive"))
      (node (ref "RCOL1") (pin "1") (pinfunction "1_1") (pintype "passive"))
      (node (ref "RCOL2") (pin "1") (pinfunction "1_1") (pintype "passive"))
      (node (ref "RCOL3") (pin "1") (pinfunction "1_1") (pintype "passive"))
      (node (ref "RCOL4") (pin "1") (pinfunction "1_1") (pintype "passive"))
      (node (ref "RCOL5") (pin "1") (pinfunction "1_1") (pintype "passive"))
      (node (ref "RCOL6") (pin "1") (pinfunction "1_1") (pintype "passive"))
      (node (ref "RCOL7") (pin "1") (pinfunction "1_1") (pintype "passive"))
      (node (ref "RCOL8") (pin "1") (pinfunction "1_1") (pintype "passive"))
      (node (ref "RCOL9") (pin "1") (pinfunction "1_1") (pintype "passive"))
      (node (ref "RCOLA") (pin "1") (pinfunction "1_1") (pintype "passive"))
    )
    (net (code "21") (name "Net-(D00-A)") (class "Default")
      (node (ref "D00") (pin "1") (pinfunction "A_1") (pintype "passive"))
      (node (ref "SW00") (pin "2") (pinfunction "2_2") (pintype "passive"))
    )
    (net (code "22") (name "Net-(D0A-A)") (class "Default")
      (node (ref "D0A") (pin "1") (pinfunction "A_1") (pintype "passive"))
      (node (ref "SW0A") (pin "2") (pinfunction "2_2") (pintype "passive"))
    )
    (net (code "23") (name "Net-(D01-A)") (class "Default")
      (node (ref "D01") (pin "1") (pinfunction "A_1") (pintype "passive"))
      (node (ref "SW01") (pin "2") (pinfunction "2_2") (pintype "passive"))
    )
    (net (code "24") (name "Net-(D1A-A)") (class "Default")
      (node (ref "D1A") (pin "1") (pinfunction "A_1") (pintype "passive"))
      (node (ref "SW1A") (pin "2") (pinfunction "2_2") (pintype "passive"))
    )
    (net (code "25") (name "Net-(D02-A)") (class "Default")
      (node (ref "D02") (pin "1") (pinfunction "A_1") (pintype "passive"))
      (node (ref "SW02") (pin "2") (pinfunction "2_2") (pintype "passive"))
    )
    (net (code "26") (name "Net-(D2A-A)") (class "Default")
      (node (ref "D2A") (pin "1") (pinfunction "A_1") (pintype "passive"))
      (node (ref "SW2A") (pin "2") (pinfunction "2_2") (pintype "passive"))
    )
    (net (code "27") (name "Net-(D03-A)") (class "Default")
      (node (ref "D03") (pin "1") (pinfunction "A_1") (pintype "passive"))
      (node (ref "SW03") (pin "2") (pinfunction "2_2") (pintype "passive"))
    )
    (net (code "28") (name "Net-(D3A-A)") (class "Default")
      (node (ref "D3A") (pin "1") (pinfunction "A_1") (pintype "passive"))
      (node (ref "SW3A") (pin "2") (pinfunction "2_2") (pintype "passive"))
    )
    (net (code "29") (name "Net-(D4A-A)") (class "Default")
      (node (ref "D4A") (pin "1") (pinfunction "A_1") (pintype "passive"))
      (node (ref "SW4A") (pin "2") (pinfunction "2_2") (pintype "passive"))
    )
    (net (code "30") (name "Net-(D5A-A)") (class "Default")
      (node (ref "D5A") (pin "1") (pinfunction "A_1") (pintype "passive"))
      (node (ref "SW5A") (pin "2") (pinfunction "2_2") (pintype "passive"))
    )
    (net (code "31") (name "Net-(D07-A)") (class "Default")
      (node (ref "D07") (pin "1") (pinfunction "A_1") (pintype "passive"))
      (node (ref "SW07") (pin "2") (pinfunction "2_2") (pintype "passive"))
    )
    (net (code "32") (name "Net-(D08-A)") (class "Default")
      (node (ref "D08") (pin "1") (pinfunction "A_1") (pintype "passive"))
      (node (ref "SW08") (pin "2") (pinfunction "2_2") (pintype "passive"))
    )
    (net (code "33") (name "Net-(D09-A)") (class "Default")
      (node (ref "D09") (pin "1") (pinfunction "A_1") (pintype "passive"))
      (node (ref "SW09") (pin "2") (pinfunction "2_2") (pintype "passive"))
    )
    (net (code "34") (name "Net-(D10-A)") (class "Default")
      (node (ref "D10") (pin "1") (pinfunction "A_1") (pintype "passive"))
      (node (ref "SW10") (pin "2") (pinfunction "2_2") (pintype "passive"))
    )
    (net (code "35") (name "Net-(D11-A)") (class "Default")
      (node (ref "D11") (pin "1") (pinfunction "A_1") (pintype "passive"))
      (node (ref "SW11") (pin "2") (pinfunction "2_2") (pintype "passive"))
    )
    (net (code "36") (name "Net-(D12-A)") (class "Default")
      (node (ref "D12") (pin "1") (pinfunction "A_1") (pintype "passive"))
      (node (ref "SW12") (pin "2") (pinfunction "2_2") (pintype "passive"))
    )
    (net (code "37") (name "Net-(D13-A)") (class "Default")
      (node (ref "D13") (pin "1") (pinfunction "A_1") (pintype "passive"))
      (node (ref "SW13") (pin "2") (pinfunction "2_2") (pintype "passive"))
    )
    (net (code "38") (name "Net-(D14-A)") (class "Default")
      (node (ref "D14") (pin "1") (pinfunction "A_1") (pintype "passive"))
      (node (ref "SW14") (pin "2") (pinfunction "2_2") (pintype "passive"))
    )
    (net (code "39") (name "Net-(D15-A)") (class "Default")
      (node (ref "D15") (pin "1") (pinfunction "A_1") (pintype "passive"))
      (node (ref "SW15") (pin "2") (pinfunction "2_2") (pintype "passive"))
    )
    (net (code "40") (name "Net-(D16-A)") (class "Default")
      (node (ref "D16") (pin "1") (pinfunction "A_1") (pintype "passive"))
      (node (ref "SW16") (pin "2") (pinfunction "2_2") (pintype "passive"))
    )
    (net (code "41") (name "Net-(D17-A)") (class "Default")
      (node (ref "D17") (pin "1") (pinfunction "A_1") (pintype "passive"))
      (node (ref "SW17") (pin "2") (pinfunction "2_2") (pintype "passive"))
    )
    (net (code "42") (name "Net-(D18-A)") (class "Default")
      (node (ref "D18") (pin "1") (pinfunction "A_1") (pintype "passive"))
      (node (ref "SW18") (pin "2") (pinfunction "2_2") (pintype "passive"))
    )
    (net (code "43") (name "Net-(D19-A)") (class "Default")
      (node (ref "D19") (pin "1") (pinfunction "A_1") (pintype "passive"))
      (node (ref "SW19") (pin "2") (pinfunction "2_2") (pintype "passive"))
    )
    (net (code "44") (name "Net-(D20-A)") (class "Default")
      (node (ref "D20") (pin "1") (pinfunction "A_1") (pintype "passive"))
      (node (ref "SW20") (pin "2") (pinfunction "2_2") (pintype "passive"))
    )
    (net (code "45") (name "Net-(D21-A)") (class "Default")
      (node (ref "D21") (pin "1") (pinfunction "A_1") (pintype "passive"))
      (node (ref "SW21") (pin "2") (pinfunction "2_2") (pintype "passive"))
    )
    (net (code "46") (name "Net-(D22-A)") (class "Default")
      (node (ref "D22") (pin "1") (pinfunction "A_1") (pintype "passive"))
      (node (ref "SW22") (pin "2") (pinfunction "2_2") (pintype "passive"))
    )
    (net (code "47") (name "Net-(D23-A)") (class "Default")
      (node (ref "D23") (pin "1") (pinfunction "A_1") (pintype "passive"))
      (node (ref "SW23") (pin "2") (pinfunction "2_2") (pintype "passive"))
    )
    (net (code "48") (name "Net-(D24-A)") (class "Default")
      (node (ref "D24") (pin "1") (pinfunction "A_1") (pintype "passive"))
      (node (ref "SW24") (pin "2") (pinfunction "2_2") (pintype "passive"))
    )
    (net (code "49") (name "Net-(D25-A)") (class "Default")
      (node (ref "D25") (pin "1") (pinfunction "A_1") (pintype "passive"))
      (node (ref "SW25") (pin "2") (pinfunction "2_2") (pintype "passive"))
    )
    (net (code "50") (name "Net-(D26-A)") (class "Default")
      (node (ref "D26") (pin "1") (pinfunction "A_1") (pintype "passive"))
      (node (ref "SW26") (pin "2") (pinfunction "2_2") (pintype "passive"))
    )
    (net (code "51") (name "Net-(D27-A)") (class "Default")
      (node (ref "D27") (pin "1") (pinfunction "A_1") (pintype "passive"))
      (node (ref "SW27") (pin "2") (pinfunction "2_2") (pintype "passive"))
    )
    (net (code "52") (name "Net-(D28-A)") (class "Default")
      (node (ref "D28") (pin "1") (pinfunction "A_1") (pintype "passive"))
      (node (ref "SW28") (pin "2") (pinfunction "2_2") (pintype "passive"))
    )
    (net (code "53") (name "Net-(D29-A)") (class "Default")
      (node (ref "D29") (pin "1") (pinfunction "A_1") (pintype "passive"))
      (node (ref "SW29") (pin "2") (pinfunction "2_2") (pintype "passive"))
    )
    (net (code "54") (name "Net-(D30-A)") (class "Default")
      (node (ref "D30") (pin "1") (pinfunction "A_1") (pintype "passive"))
      (node (ref "SW30") (pin "2") (pinfunction "2_2") (pintype "passive"))
    )
    (net (code "55") (name "Net-(D31-A)") (class "Default")
      (node (ref "D31") (pin "1") (pinfunction "A_1") (pintype "passive"))
      (node (ref "SW31") (pin "2") (pinfunction "2_2") (pintype "passive"))
    )
    (net (code "56") (name "Net-(D32-A)") (class "Default")
      (node (ref "D32") (pin "1") (pinfunction "A_1") (pintype "passive"))
      (node (ref "SW32") (pin "2") (pinfunction "2_2") (pintype "passive"))
    )
    (net (code "57") (name "Net-(D33-A)") (class "Default")
      (node (ref "D33") (pin "1") (pinfunction "A_1") (pintype "passive"))
      (node (ref "SW33") (pin "2") (pinfunction "2_2") (pintype "passive"))
    )
    (net (code "58") (name "Net-(D34-A)") (class "Default")
      (node (ref "D34") (pin "1") (pinfunction "A_1") (pintype "passive"))
      (node (ref "SW34") (pin "2") (pinfunction "2_2") (pintype "passive"))
    )
    (net (code "59") (name "Net-(D35-A)") (class "Default")
      (node (ref "D35") (pin "1") (pinfunction "A_1") (pintype "passive"))
      (node (ref "SW35") (pin "2") (pinfunction "2_2") (pintype "passive"))
    )
    (net (code "60") (name "Net-(D36-A)") (class "Default")
      (node (ref "D36") (pin "1") (pinfunction "A_1") (pintype "passive"))
      (node (ref "SW36") (pin "2") (pinfunction "2_2") (pintype "passive"))
    )
    (net (code "61") (name "Net-(D37-A)") (class "Default")
      (node (ref "D37") (pin "1") (pinfunction "A_1") (pintype "passive"))
      (node (ref "SW37") (pin "2") (pinfunction "2_2") (pintype "passive"))
    )
    (net (code "62") (name "Net-(D38-A)") (class "Default")
      (node (ref "D38") (pin "1") (pinfunction "A_1") (pintype "passive"))
      (node (ref "SW38") (pin "2") (pinfunction "2_2") (pintype "passive"))
    )
    (net (code "63") (name "Net-(D39-A)") (class "Default")
      (node (ref "D39") (pin "1") (pinfunction "A_1") (pintype "passive"))
      (node (ref "SW39") (pin "2") (pinfunction "2_2") (pintype "passive"))
    )
    (net (code "64") (name "Net-(D40-A)") (class "Default")
      (node (ref "D40") (pin "1") (pinfunction "A_1") (pintype "passive"))
      (node (ref "SW40") (pin "2") (pinfunction "2_2") (pintype "passive"))
    )
    (net (code "65") (name "Net-(D41-A)") (class "Default")
      (node (ref "D41") (pin "1") (pinfunction "A_1") (pintype "passive"))
      (node (ref "SW41") (pin "2") (pinfunction "2_2") (pintype "passive"))
    )
    (net (code "66") (name "Net-(D42-A)") (class "Default")
      (node (ref "D42") (pin "1") (pinfunction "A_1") (pintype "passive"))
      (node (ref "SW42") (pin "2") (pinfunction "2_2") (pintype "passive"))
    )
    (net (code "67") (name "Net-(D43-A)") (class "Default")
      (node (ref "D43") (pin "1") (pinfunction "A_1") (pintype "passive"))
      (node (ref "SW43") (pin "2") (pinfunction "2_2") (pintype "passive"))
    )
    (net (code "68") (name "Net-(D44-A)") (class "Default")
      (node (ref "D44") (pin "1") (pinfunction "A_1") (pintype "passive"))
      (node (ref "SW44") (pin "2") (pinfunction "2_2") (pintype "passive"))
    )
    (net (code "69") (name "Net-(D45-A)") (class "Default")
      (node (ref "D45") (pin "1") (pinfunction "A_1") (pintype "passive"))
      (node (ref "SW45") (pin "2") (pinfunction "2_2") (pintype "passive"))
    )
    (net (code "70") (name "Net-(D46-A)") (class "Default")
      (node (ref "D46") (pin "1") (pinfunction "A_1") (pintype "passive"))
      (node (ref "SW46") (pin "2") (pinfunction "2_2") (pintype "passive"))
    )
    (net (code "71") (name "Net-(D47-A)") (class "Default")
      (node (ref "D47") (pin "1") (pinfunction "A_1") (pintype "passive"))
      (node (ref "SW47") (pin "2") (pinfunction "2_2") (pintype "passive"))
    )
    (net (code "72") (name "Net-(D48-A)") (class "Default")
      (node (ref "D48") (pin "1") (pinfunction "A_1") (pintype "passive"))
      (node (ref "SW48") (pin "2") (pinfunction "2_2") (pintype "passive"))
    )
    (net (code "73") (name "Net-(D49-A)") (class "Default")
      (node (ref "D49") (pin "1") (pinfunction "A_1") (pintype "passive"))
      (node (ref "SW49") (pin "2") (pinfunction "2_2") (pintype "passive"))
    )
    (net (code "74") (name "Net-(D50-A)") (class "Default")
      (node (ref "D50") (pin "1") (pinfunction "A_1") (pintype "passive"))
      (node (ref "SW50") (pin "2") (pinfunction "2_2") (pintype "passive"))
    )
    (net (code "75") (name "Net-(D51-A)") (class "Default")
      (node (ref "D51") (pin "1") (pinfunction "A_1") (pintype "passive"))
      (node (ref "SW51") (pin "2") (pinfunction "2_2") (pintype "passive"))
    )
    (net (code "76") (name "Net-(D52-A)") (class "Default")
      (node (ref "D52") (pin "1") (pinfunction "A_1") (pintype "passive"))
      (node (ref "SW52") (pin "2") (pinfunction "2_2") (pintype "passive"))
    )
    (net (code "77") (name "Net-(D53-A)") (class "Default")
      (node (ref "D53") (pin "1") (pinfunction "A_1") (pintype "passive"))
      (node (ref "SW53") (pin "2") (pinfunction "2_2") (pintype "passive"))
    )
    (net (code "78") (name "Net-(D54-A)") (class "Default")
      (node (ref "D54") (pin "1") (pinfunction "A_1") (pintype "passive"))
      (node (ref "SW54") (pin "2") (pinfunction "2_2") (pintype "passive"))
    )
    (net (code "79") (name "Net-(D55-A)") (class "Default")
      (node (ref "D55") (pin "1") (pinfunction "A_1") (pintype "passive"))
      (node (ref "SW55") (pin "2") (pinfunction "2_2") (pintype "passive"))
    )
    (net (code "80") (name "Net-(D56-A)") (class "Default")
      (node (ref "D56") (pin "1") (pinfunction "A_1") (pintype "passive"))
      (node (ref "SW56") (pin "2") (pinfunction "2_2") (pintype "passive"))
    )
    (net (code "81") (name "Net-(D57-A)") (class "Default")
      (node (ref "D57") (pin "1") (pinfunction "A_1") (pintype "passive"))
      (node (ref "SW57") (pin "2") (pinfunction "2_2") (pintype "passive"))
    )
    (net (code "82") (name "Net-(D58-A)") (class "Default")
      (node (ref "D58") (pin "1") (pinfunction "A_1") (pintype "passive"))
      (node (ref "SW58") (pin "2") (pinfunction "2_2") (pintype "passive"))
    )
    (net (code "83") (name "Net-(D59-A)") (class "Default")
      (node (ref "D59") (pin "1") (pinfunction "A_1") (pintype "passive"))
      (node (ref "SW59") (pin "2") (pinfunction "2_2") (pintype "passive"))
    )
  )
)
